# ArduinoISP.net
KiCad netlist of a schematic drawn in EAGLE
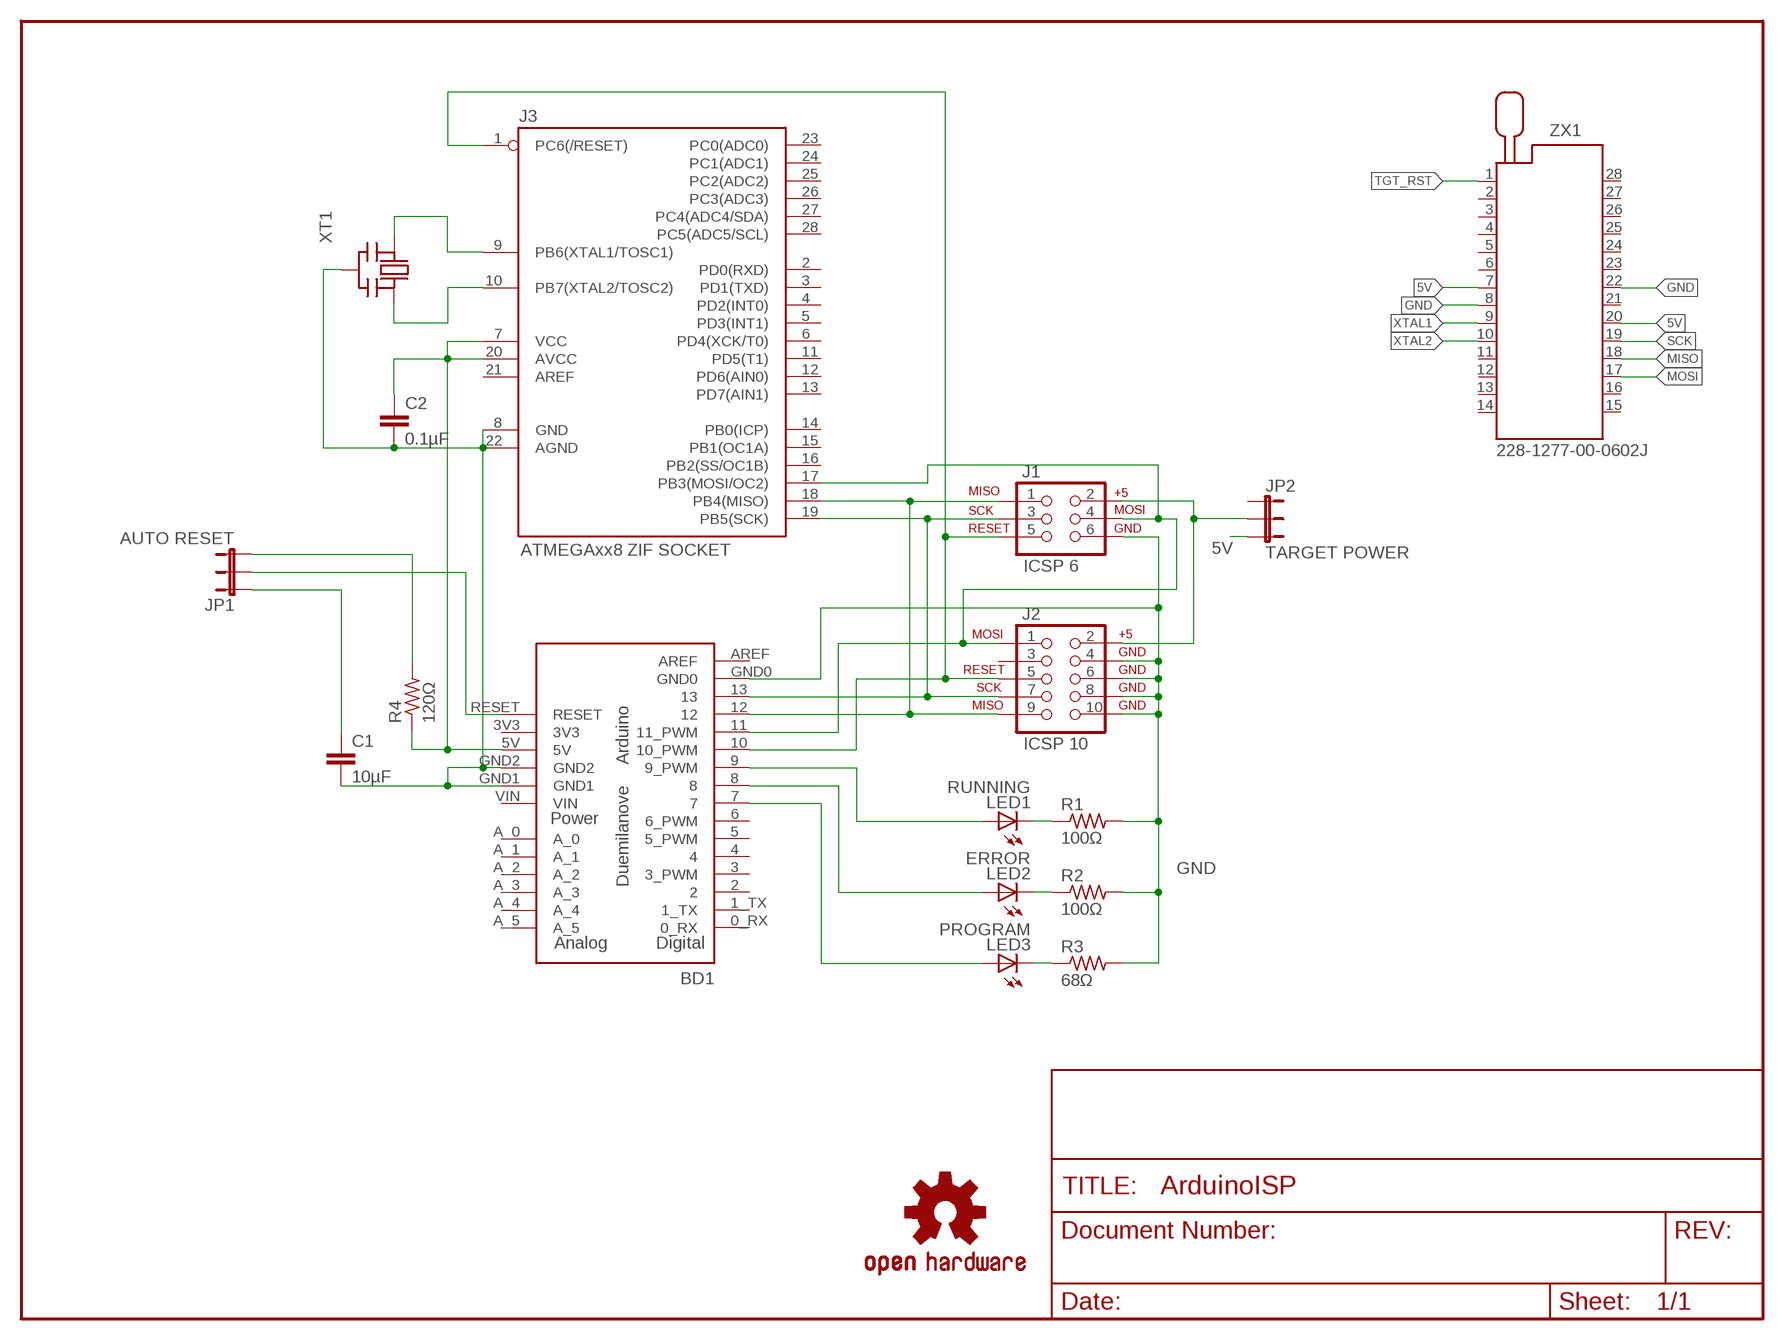
[diagram p0: schematic, sheet 1]

(export (version "E")
  (design (tool "Eeschema 10.0.6"))
  (components
    (comp (ref "BD1")
      (value "ARDUINO-USBOCTAGONAL_PADS")
      (footprint "eagle-import:SHIELD-OCTAGONALPAD")
      (libsource (lib "eagle-import") (part "ARDUINO-USBOCTAGONAL_PADS"))
    )
    (comp (ref "C1")
      (value "10µF")
      (footprint "eagle-import:C050-055X075")
      (libsource (lib "eagle-import") (part "C-EU050-055X075"))
    )
    (comp (ref "C2")
      (value "0.1µF")
      (footprint "eagle-import:C025-024X044")
      (libsource (lib "eagle-import") (part "C-EU025-024X044"))
    )
    (comp (ref "J1")
      (value "ICSP 6")
      (footprint "eagle-import:2X3-NS")
      (libsource (lib "eagle-import") (part "AVR_SPI_PRG_6NS"))
    )
    (comp (ref "J2")
      (value "ICSP 10")
      (footprint "eagle-import:AVR_ICSP")
      (libsource (lib "eagle-import") (part "AVR_SPI_PROG2PTH"))
    )
    (comp (ref "J3")
      (value "ATMEGAxx8 ZIF SOCKET")
      (footprint "eagle-import:DIL28-3-ZIF_SOCKET")
      (libsource (lib "eagle-import") (part "AVR-MEGA8-PZIF_SOCKET"))
    )
    (comp (ref "JP1")
      (value "AUTO RESET")
      (footprint "eagle-import:1X03")
      (libsource (lib "eagle-import") (part "JUMPER-3PTH"))
    )
    (comp (ref "JP2")
      (value "TARGET POWER")
      (footprint "eagle-import:1X03")
      (libsource (lib "eagle-import") (part "JUMPER-3PTH"))
    )
    (comp (ref "LED1")
      (value "RUNNING")
      (footprint "eagle-import:LED5MM")
      (libsource (lib "eagle-import") (part "LED5MM"))
    )
    (comp (ref "LED2")
      (value "ERROR")
      (footprint "eagle-import:LED5MM")
      (libsource (lib "eagle-import") (part "LED5MM"))
    )
    (comp (ref "LED3")
      (value "PROGRAM")
      (footprint "eagle-import:LED5MM")
      (libsource (lib "eagle-import") (part "LED5MM"))
    )
    (comp (ref "R1")
      (value "100Ω")
      (footprint "eagle-import:0204_7")
      (libsource (lib "eagle-import") (part "R-US_0204/7"))
    )
    (comp (ref "R2")
      (value "100Ω")
      (footprint "eagle-import:0204_7")
      (libsource (lib "eagle-import") (part "R-US_0204/7"))
    )
    (comp (ref "R3")
      (value "68Ω")
      (footprint "eagle-import:0204_7")
      (libsource (lib "eagle-import") (part "R-US_0204/7"))
    )
    (comp (ref "R4")
      (value "120Ω")
      (footprint "eagle-import:0204_7")
      (libsource (lib "eagle-import") (part "R-US_0204/7"))
    )
    (comp (ref "U$2")
      (value "OSHW-LOGOM")
      (footprint "eagle-import:OSHW-LOGO-M")
      (libsource (lib "eagle-import") (part "OSHW-LOGOM"))
    )
    (comp (ref "XT1")
      (value "CERMOSCILL-THM")
      (footprint "eagle-import:CERM_OSC")
      (libsource (lib "eagle-import") (part "CERMOSCILL-THM"))
    )
    (comp (ref "ZX1")
      (value "228-1277-00-0602J")
      (footprint "eagle-import:228-1277-00-0602J")
      (fields (field (name "MF") "3M"))
      (libsource (lib "eagle-import") (part "228-?00-0602J1277-"))
    )
  )
  (nets
    (net (code "1") (name "/3V3") (class "Default")
      (node (ref "BD1") (pin "3V3") (pinfunction "3V3_3V3") (pintype "power_in"))
    )
    (net (code "2") (name "/VIN") (class "Default")
      (node (ref "BD1") (pin "VIN") (pinfunction "VIN_VIN") (pintype "power_in"))
    )
    (net (code "3") (name "5V") (class "Default")
      (node (ref "BD1") (pin "5V") (pinfunction "5V_5V") (pintype "power_in"))
      (node (ref "C2") (pin "1") (pinfunction "1_1") (pintype "passive"))
      (node (ref "J3") (pin "20") (pinfunction "AVCC_20") (pintype "bidirectional"))
      (node (ref "J3") (pin "7") (pinfunction "VCC_7") (pintype "bidirectional"))
      (node (ref "JP2") (pin "3") (pinfunction "3_3") (pintype "passive"))
      (node (ref "R4") (pin "1") (pinfunction "1_1") (pintype "passive"))
      (node (ref "ZX1") (pin "20") (pinfunction "20_20") (pintype "passive"))
      (node (ref "ZX1") (pin "7") (pinfunction "7_7") (pintype "passive"))
    )
    (net (code "4") (name "GND") (class "Default")
      (node (ref "BD1") (pin "GND0") (pinfunction "GND0_GND0") (pintype "power_in"))
      (node (ref "BD1") (pin "GND1") (pinfunction "GND1_GND1") (pintype "power_in"))
      (node (ref "BD1") (pin "GND2") (pinfunction "GND2_GND2") (pintype "power_in"))
      (node (ref "C1") (pin "2") (pinfunction "2_2") (pintype "passive"))
      (node (ref "C2") (pin "2") (pinfunction "2_2") (pintype "passive"))
      (node (ref "J1") (pin "6") (pinfunction "6_6") (pintype "passive"))
      (node (ref "J2") (pin "10") (pinfunction "10_10") (pintype "passive"))
      (node (ref "J2") (pin "4") (pinfunction "4_4") (pintype "passive"))
      (node (ref "J2") (pin "6") (pinfunction "6_6") (pintype "passive"))
      (node (ref "J2") (pin "8") (pinfunction "8_8") (pintype "passive"))
      (node (ref "J3") (pin "22") (pinfunction "AGND_22") (pintype "bidirectional"))
      (node (ref "J3") (pin "8") (pinfunction "GND_8") (pintype "bidirectional"))
      (node (ref "R1") (pin "2") (pinfunction "2_2") (pintype "passive"))
      (node (ref "R2") (pin "2") (pinfunction "2_2") (pintype "passive"))
      (node (ref "R3") (pin "2") (pinfunction "2_2") (pintype "passive"))
      (node (ref "XT1") (pin "P$2") (pinfunction "GND_P$2") (pintype "bidirectional"))
      (node (ref "ZX1") (pin "22") (pinfunction "22_22") (pintype "passive"))
      (node (ref "ZX1") (pin "8") (pinfunction "8_8") (pintype "passive"))
    )
    (net (code "5") (name "MISO") (class "Default")
      (node (ref "BD1") (pin "12") (pinfunction "12_12") (pintype "bidirectional"))
      (node (ref "J1") (pin "1") (pinfunction "1_1") (pintype "passive"))
      (node (ref "J2") (pin "9") (pinfunction "9_9") (pintype "passive"))
      (node (ref "J3") (pin "18") (pinfunction "PB4(MISO)_18") (pintype "bidirectional"))
      (node (ref "ZX1") (pin "18") (pinfunction "18_18") (pintype "passive"))
    )
    (net (code "6") (name "MOSI") (class "Default")
      (node (ref "BD1") (pin "11") (pinfunction "11_PWM_11") (pintype "bidirectional"))
      (node (ref "J1") (pin "4") (pinfunction "4_4") (pintype "passive"))
      (node (ref "J2") (pin "1") (pinfunction "1_1") (pintype "passive"))
      (node (ref "J3") (pin "17") (pinfunction "PB3(MOSI/OC2)_17") (pintype "bidirectional"))
      (node (ref "ZX1") (pin "17") (pinfunction "17_17") (pintype "passive"))
    )
    (net (code "7") (name "Net-(BD1-9_PWM)") (class "Default")
      (node (ref "BD1") (pin "9") (pinfunction "9_PWM_9") (pintype "bidirectional"))
      (node (ref "LED1") (pin "A") (pinfunction "A_A") (pintype "passive"))
    )
    (net (code "8") (name "Net-(BD1-Pad7)") (class "Default")
      (node (ref "BD1") (pin "7") (pinfunction "7_7") (pintype "bidirectional"))
      (node (ref "LED3") (pin "A") (pinfunction "A_A") (pintype "passive"))
    )
    (net (code "9") (name "Net-(BD1-Pad8)") (class "Default")
      (node (ref "BD1") (pin "8") (pinfunction "8_8") (pintype "bidirectional"))
      (node (ref "LED2") (pin "A") (pinfunction "A_A") (pintype "passive"))
    )
    (net (code "10") (name "Net-(BD1-PadRESET)") (class "Default")
      (node (ref "BD1") (pin "RESET") (pinfunction "RESET_RESET") (pintype "input"))
      (node (ref "JP1") (pin "2") (pinfunction "2_2") (pintype "passive"))
    )
    (net (code "11") (name "Net-(C1-Pad1)") (class "Default")
      (node (ref "C1") (pin "1") (pinfunction "1_1") (pintype "passive"))
      (node (ref "JP1") (pin "1") (pinfunction "1_1") (pintype "passive"))
    )
    (net (code "12") (name "Net-(J1-Pad2)") (class "Default")
      (node (ref "J1") (pin "2") (pinfunction "2_2") (pintype "passive"))
      (node (ref "J2") (pin "2") (pinfunction "2_2") (pintype "passive"))
      (node (ref "JP2") (pin "2") (pinfunction "2_2") (pintype "passive"))
    )
    (net (code "13") (name "Net-(JP1-Pad3)") (class "Default")
      (node (ref "JP1") (pin "3") (pinfunction "3_3") (pintype "passive"))
      (node (ref "R4") (pin "2") (pinfunction "2_2") (pintype "passive"))
    )
    (net (code "14") (name "Net-(LED1-C)") (class "Default")
      (node (ref "LED1") (pin "K") (pinfunction "C_K") (pintype "passive"))
      (node (ref "R1") (pin "1") (pinfunction "1_1") (pintype "passive"))
    )
    (net (code "15") (name "Net-(LED2-C)") (class "Default")
      (node (ref "LED2") (pin "K") (pinfunction "C_K") (pintype "passive"))
      (node (ref "R2") (pin "1") (pinfunction "1_1") (pintype "passive"))
    )
    (net (code "16") (name "Net-(LED3-C)") (class "Default")
      (node (ref "LED3") (pin "K") (pinfunction "C_K") (pintype "passive"))
      (node (ref "R3") (pin "1") (pinfunction "1_1") (pintype "passive"))
    )
    (net (code "17") (name "SCK") (class "Default")
      (node (ref "BD1") (pin "13") (pinfunction "13_13") (pintype "bidirectional"))
      (node (ref "J1") (pin "3") (pinfunction "3_3") (pintype "passive"))
      (node (ref "J2") (pin "7") (pinfunction "7_7") (pintype "passive"))
      (node (ref "J3") (pin "19") (pinfunction "PB5(SCK)_19") (pintype "bidirectional"))
      (node (ref "ZX1") (pin "19") (pinfunction "19_19") (pintype "passive"))
    )
    (net (code "18") (name "TGT_RST") (class "Default")
      (node (ref "BD1") (pin "10") (pinfunction "10_PWM_10") (pintype "bidirectional"))
      (node (ref "J1") (pin "5") (pinfunction "5_5") (pintype "passive"))
      (node (ref "J2") (pin "5") (pinfunction "5_5") (pintype "passive"))
      (node (ref "J3") (pin "1") (pinfunction "PC6(/RESET)_1") (pintype "bidirectional"))
      (node (ref "ZX1") (pin "1") (pinfunction "1_1") (pintype "passive"))
    )
    (net (code "19") (name "XTAL1") (class "Default")
      (node (ref "J3") (pin "9") (pinfunction "PB6(XTAL1/TOSC1)_9") (pintype "bidirectional"))
      (node (ref "XT1") (pin "P$1") (pinfunction "IN_P$1") (pintype "bidirectional"))
      (node (ref "ZX1") (pin "9") (pinfunction "9_9") (pintype "passive"))
    )
    (net (code "20") (name "XTAL2") (class "Default")
      (node (ref "J3") (pin "10") (pinfunction "PB7(XTAL2/TOSC2)_10") (pintype "bidirectional"))
      (node (ref "XT1") (pin "P$3") (pinfunction "OUT_P$3") (pintype "bidirectional"))
      (node (ref "ZX1") (pin "10") (pinfunction "10_10") (pintype "passive"))
    )
    (net (code "21") (name "unconnected-(BD1-3_PWM-Pad3)") (class "Default")
      (node (ref "BD1") (pin "3") (pinfunction "3_PWM_3") (pintype "bidirectional"))
    )
    (net (code "22") (name "unconnected-(BD1-5_PWM-Pad5)") (class "Default")
      (node (ref "BD1") (pin "5") (pinfunction "5_PWM_5") (pintype "bidirectional"))
    )
    (net (code "23") (name "unconnected-(BD1-6_PWM-Pad6)") (class "Default")
      (node (ref "BD1") (pin "6") (pinfunction "6_PWM_6") (pintype "bidirectional"))
    )
    (net (code "24") (name "unconnected-(BD1-Pad0_RX)") (class "Default")
      (node (ref "BD1") (pin "0_RX") (pinfunction "0_RX_0_RX") (pintype "bidirectional"))
    )
    (net (code "25") (name "unconnected-(BD1-Pad1_TX)") (class "Default")
      (node (ref "BD1") (pin "1_TX") (pinfunction "1_TX_1_TX") (pintype "bidirectional"))
    )
    (net (code "26") (name "unconnected-(BD1-Pad2)") (class "Default")
      (node (ref "BD1") (pin "2") (pinfunction "2_2") (pintype "bidirectional"))
    )
    (net (code "27") (name "unconnected-(BD1-Pad4)") (class "Default")
      (node (ref "BD1") (pin "4") (pinfunction "4_4") (pintype "bidirectional"))
    )
    (net (code "28") (name "unconnected-(BD1-PadAREF)") (class "Default")
      (node (ref "BD1") (pin "AREF") (pinfunction "AREF_AREF") (pintype "bidirectional"))
    )
    (net (code "29") (name "unconnected-(BD1-PadA_0)") (class "Default")
      (node (ref "BD1") (pin "A_0") (pinfunction "A_0_A_0") (pintype "input"))
    )
    (net (code "30") (name "unconnected-(BD1-PadA_1)") (class "Default")
      (node (ref "BD1") (pin "A_1") (pinfunction "A_1_A_1") (pintype "input"))
    )
    (net (code "31") (name "unconnected-(BD1-PadA_2)") (class "Default")
      (node (ref "BD1") (pin "A_2") (pinfunction "A_2_A_2") (pintype "input"))
    )
    (net (code "32") (name "unconnected-(BD1-PadA_3)") (class "Default")
      (node (ref "BD1") (pin "A_3") (pinfunction "A_3_A_3") (pintype "input"))
    )
    (net (code "33") (name "unconnected-(BD1-PadA_4)") (class "Default")
      (node (ref "BD1") (pin "A_4") (pinfunction "A_4_A_4") (pintype "input"))
    )
    (net (code "34") (name "unconnected-(BD1-PadA_5)") (class "Default")
      (node (ref "BD1") (pin "A_5") (pinfunction "A_5_A_5") (pintype "input"))
    )
    (net (code "35") (name "unconnected-(J2-Pad3)") (class "Default")
      (node (ref "J2") (pin "3") (pinfunction "3_3") (pintype "passive"))
    )
    (net (code "36") (name "unconnected-(J3-AREF-Pad21)") (class "Default")
      (node (ref "J3") (pin "21") (pinfunction "AREF_21") (pintype "bidirectional"))
    )
    (net (code "37") (name "unconnected-(J3-PB0(ICP)-Pad14)") (class "Default")
      (node (ref "J3") (pin "14") (pinfunction "PB0(ICP)_14") (pintype "bidirectional"))
    )
    (net (code "38") (name "unconnected-(J3-PB1(OC1A)-Pad15)") (class "Default")
      (node (ref "J3") (pin "15") (pinfunction "PB1(OC1A)_15") (pintype "bidirectional"))
    )
    (net (code "39") (name "unconnected-(J3-PB2(SS{slash}OC1B)-Pad16)") (class "Default")
      (node (ref "J3") (pin "16") (pinfunction "PB2(SS/OC1B)_16") (pintype "bidirectional"))
    )
    (net (code "40") (name "unconnected-(J3-PC0(ADC0)-Pad23)") (class "Default")
      (node (ref "J3") (pin "23") (pinfunction "PC0(ADC0)_23") (pintype "bidirectional"))
    )
    (net (code "41") (name "unconnected-(J3-PC1(ADC1)-Pad24)") (class "Default")
      (node (ref "J3") (pin "24") (pinfunction "PC1(ADC1)_24") (pintype "bidirectional"))
    )
    (net (code "42") (name "unconnected-(J3-PC2(ADC2)-Pad25)") (class "Default")
      (node (ref "J3") (pin "25") (pinfunction "PC2(ADC2)_25") (pintype "bidirectional"))
    )
    (net (code "43") (name "unconnected-(J3-PC3(ADC3)-Pad26)") (class "Default")
      (node (ref "J3") (pin "26") (pinfunction "PC3(ADC3)_26") (pintype "bidirectional"))
    )
    (net (code "44") (name "unconnected-(J3-PC4(ADC4{slash}SDA)-Pad27)") (class "Default")
      (node (ref "J3") (pin "27") (pinfunction "PC4(ADC4/SDA)_27") (pintype "bidirectional"))
    )
    (net (code "45") (name "unconnected-(J3-PC5(ADC5{slash}SCL)-Pad28)") (class "Default")
      (node (ref "J3") (pin "28") (pinfunction "PC5(ADC5/SCL)_28") (pintype "bidirectional"))
    )
    (net (code "46") (name "unconnected-(J3-PD0(RXD)-Pad2)") (class "Default")
      (node (ref "J3") (pin "2") (pinfunction "PD0(RXD)_2") (pintype "bidirectional"))
    )
    (net (code "47") (name "unconnected-(J3-PD1(TXD)-Pad3)") (class "Default")
      (node (ref "J3") (pin "3") (pinfunction "PD1(TXD)_3") (pintype "bidirectional"))
    )
    (net (code "48") (name "unconnected-(J3-PD2(INT0)-Pad4)") (class "Default")
      (node (ref "J3") (pin "4") (pinfunction "PD2(INT0)_4") (pintype "bidirectional"))
    )
    (net (code "49") (name "unconnected-(J3-PD3(INT1)-Pad5)") (class "Default")
      (node (ref "J3") (pin "5") (pinfunction "PD3(INT1)_5") (pintype "bidirectional"))
    )
    (net (code "50") (name "unconnected-(J3-PD4(XCK{slash}T0)-Pad6)") (class "Default")
      (node (ref "J3") (pin "6") (pinfunction "PD4(XCK/T0)_6") (pintype "bidirectional"))
    )
    (net (code "51") (name "unconnected-(J3-PD5(T1)-Pad11)") (class "Default")
      (node (ref "J3") (pin "11") (pinfunction "PD5(T1)_11") (pintype "bidirectional"))
    )
    (net (code "52") (name "unconnected-(J3-PD6(AIN0)-Pad12)") (class "Default")
      (node (ref "J3") (pin "12") (pinfunction "PD6(AIN0)_12") (pintype "bidirectional"))
    )
    (net (code "53") (name "unconnected-(J3-PD7(AIN1)-Pad13)") (class "Default")
      (node (ref "J3") (pin "13") (pinfunction "PD7(AIN1)_13") (pintype "bidirectional"))
    )
    (net (code "54") (name "unconnected-(JP2-Pad1)") (class "Default")
      (node (ref "JP2") (pin "1") (pinfunction "1_1") (pintype "passive"))
    )
    (net (code "55") (name "unconnected-(ZX1-Pad2)") (class "Default")
      (node (ref "ZX1") (pin "2") (pinfunction "2_2") (pintype "passive"))
    )
    (net (code "56") (name "unconnected-(ZX1-Pad3)") (class "Default")
      (node (ref "ZX1") (pin "3") (pinfunction "3_3") (pintype "passive"))
    )
    (net (code "57") (name "unconnected-(ZX1-Pad4)") (class "Default")
      (node (ref "ZX1") (pin "4") (pinfunction "4_4") (pintype "passive"))
    )
    (net (code "58") (name "unconnected-(ZX1-Pad5)") (class "Default")
      (node (ref "ZX1") (pin "5") (pinfunction "5_5") (pintype "passive"))
    )
    (net (code "59") (name "unconnected-(ZX1-Pad6)") (class "Default")
      (node (ref "ZX1") (pin "6") (pinfunction "6_6") (pintype "passive"))
    )
    (net (code "60") (name "unconnected-(ZX1-Pad11)") (class "Default")
      (node (ref "ZX1") (pin "11") (pinfunction "11_11") (pintype "passive"))
    )
    (net (code "61") (name "unconnected-(ZX1-Pad12)") (class "Default")
      (node (ref "ZX1") (pin "12") (pinfunction "12_12") (pintype "passive"))
    )
    (net (code "62") (name "unconnected-(ZX1-Pad13)") (class "Default")
      (node (ref "ZX1") (pin "13") (pinfunction "13_13") (pintype "passive"))
    )
    (net (code "63") (name "unconnected-(ZX1-Pad14)") (class "Default")
      (node (ref "ZX1") (pin "14") (pinfunction "14_14") (pintype "passive"))
    )
    (net (code "64") (name "unconnected-(ZX1-Pad15)") (class "Default")
      (node (ref "ZX1") (pin "15") (pinfunction "15_15") (pintype "passive"))
    )
    (net (code "65") (name "unconnected-(ZX1-Pad16)") (class "Default")
      (node (ref "ZX1") (pin "16") (pinfunction "16_16") (pintype "passive"))
    )
    (net (code "66") (name "unconnected-(ZX1-Pad21)") (class "Default")
      (node (ref "ZX1") (pin "21") (pinfunction "21_21") (pintype "passive"))
    )
    (net (code "67") (name "unconnected-(ZX1-Pad23)") (class "Default")
      (node (ref "ZX1") (pin "23") (pinfunction "23_23") (pintype "passive"))
    )
    (net (code "68") (name "unconnected-(ZX1-Pad24)") (class "Default")
      (node (ref "ZX1") (pin "24") (pinfunction "24_24") (pintype "passive"))
    )
    (net (code "69") (name "unconnected-(ZX1-Pad25)") (class "Default")
      (node (ref "ZX1") (pin "25") (pinfunction "25_25") (pintype "passive"))
    )
    (net (code "70") (name "unconnected-(ZX1-Pad26)") (class "Default")
      (node (ref "ZX1") (pin "26") (pinfunction "26_26") (pintype "passive"))
    )
    (net (code "71") (name "unconnected-(ZX1-Pad27)") (class "Default")
      (node (ref "ZX1") (pin "27") (pinfunction "27_27") (pintype "passive"))
    )
    (net (code "72") (name "unconnected-(ZX1-Pad28)") (class "Default")
      (node (ref "ZX1") (pin "28") (pinfunction "28_28") (pintype "passive"))
    )
  )
)
